# STM32.net
KiCad netlist of a schematic drawn in Altium Designer
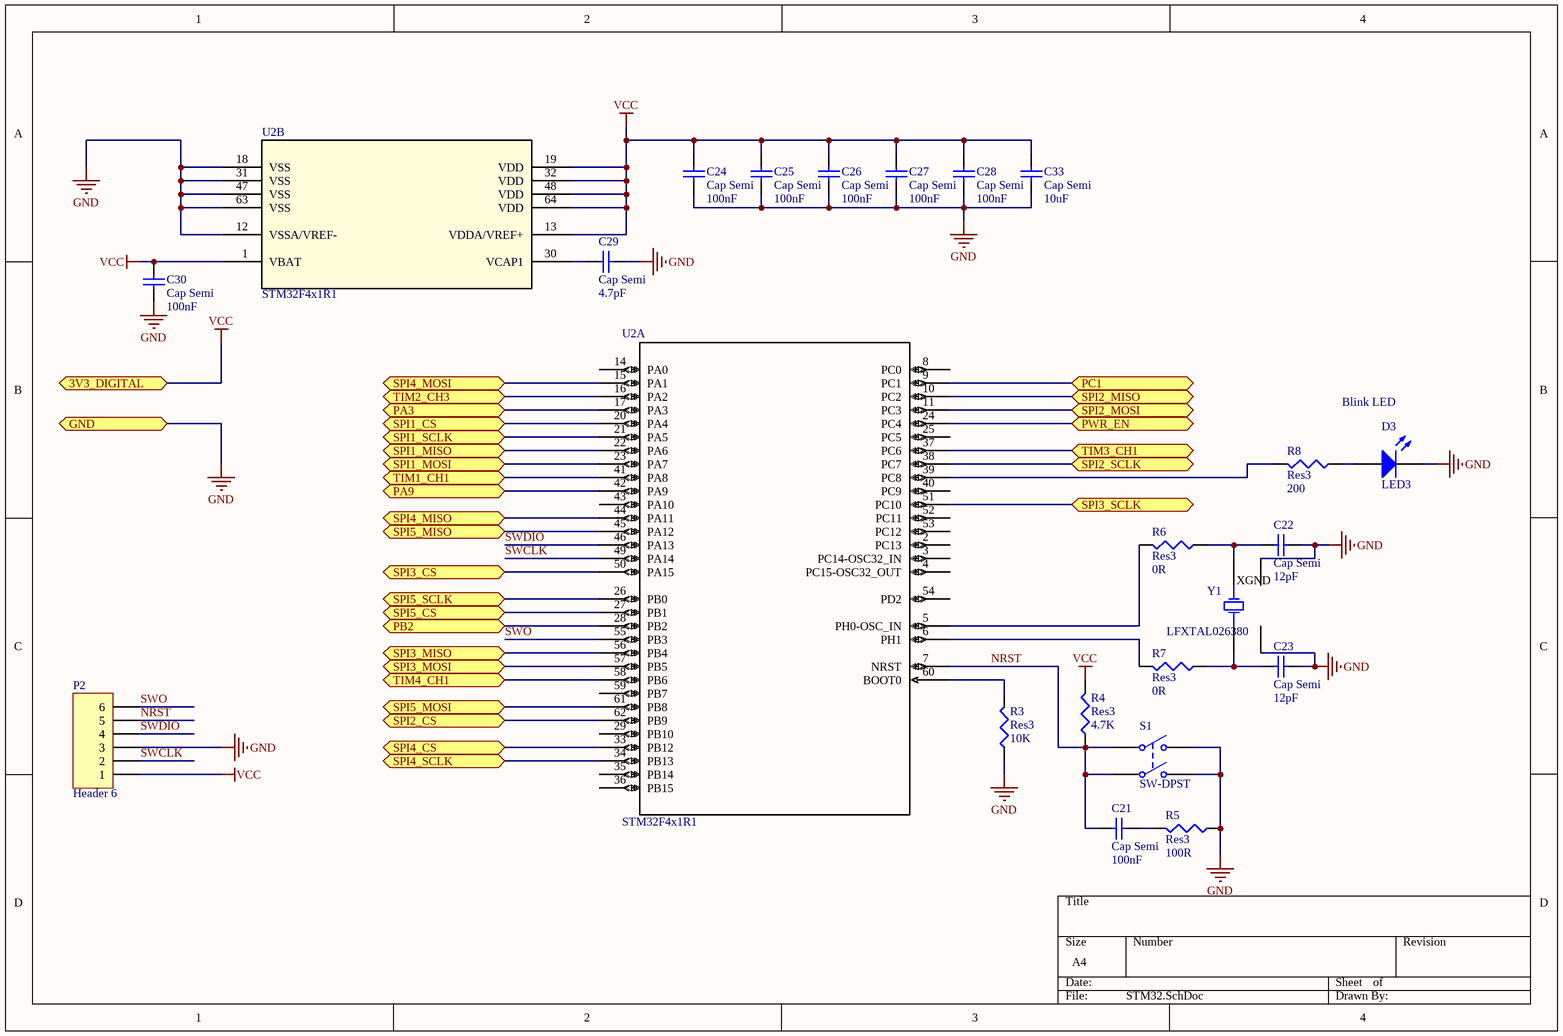
[diagram p0: STM32.SchDoc]

(export (version "E")
  (design (tool "Eeschema 10.0.6"))
  (components
    (comp (ref "C21")
      (value "Cap Semi")
      (footprint "C1206")
      (description "Capacitor (Semiconductor SIM Model)")
      (fields (field (name "ALTIUM_VALUE") "100nF") (field (name "PUBLISHER") "Altium Limited"))
      (libsource (lib "Miscellaneous Devices") (part "Cap Semi"))
    )
    (comp (ref "C22")
      (value "Cap Semi")
      (footprint "C1206")
      (description "Capacitor (Semiconductor SIM Model)")
      (fields (field (name "ALTIUM_VALUE") "12pF") (field (name "PUBLISHER") "Altium Limited"))
      (libsource (lib "Miscellaneous Devices") (part "Cap Semi"))
    )
    (comp (ref "C23")
      (value "Cap Semi")
      (footprint "C1206")
      (description "Capacitor (Semiconductor SIM Model)")
      (fields (field (name "ALTIUM_VALUE") "12pF") (field (name "PUBLISHER") "Altium Limited"))
      (libsource (lib "Miscellaneous Devices") (part "Cap Semi"))
    )
    (comp (ref "C24")
      (value "Cap Semi")
      (footprint "C1206")
      (description "Capacitor (Semiconductor SIM Model)")
      (fields (field (name "ALTIUM_VALUE") "100nF") (field (name "PUBLISHER") "Altium Limited"))
      (libsource (lib "Miscellaneous Devices") (part "Cap Semi"))
    )
    (comp (ref "C25")
      (value "Cap Semi")
      (footprint "C1206")
      (description "Capacitor (Semiconductor SIM Model)")
      (fields (field (name "ALTIUM_VALUE") "100nF") (field (name "PUBLISHER") "Altium Limited"))
      (libsource (lib "Miscellaneous Devices") (part "Cap Semi"))
    )
    (comp (ref "C26")
      (value "Cap Semi")
      (footprint "C1206")
      (description "Capacitor (Semiconductor SIM Model)")
      (fields (field (name "ALTIUM_VALUE") "100nF") (field (name "PUBLISHER") "Altium Limited"))
      (libsource (lib "Miscellaneous Devices") (part "Cap Semi"))
    )
    (comp (ref "C27")
      (value "Cap Semi")
      (footprint "C1206")
      (description "Capacitor (Semiconductor SIM Model)")
      (fields (field (name "ALTIUM_VALUE") "100nF") (field (name "PUBLISHER") "Altium Limited"))
      (libsource (lib "Miscellaneous Devices") (part "Cap Semi"))
    )
    (comp (ref "C28")
      (value "Cap Semi")
      (footprint "C1206")
      (description "Capacitor (Semiconductor SIM Model)")
      (fields (field (name "ALTIUM_VALUE") "100nF") (field (name "PUBLISHER") "Altium Limited"))
      (libsource (lib "Miscellaneous Devices") (part "Cap Semi"))
    )
    (comp (ref "C29")
      (value "Cap Semi")
      (footprint "C1206")
      (description "Capacitor (Semiconductor SIM Model)")
      (fields (field (name "ALTIUM_VALUE") "4.7pF") (field (name "PUBLISHER") "Altium Limited"))
      (libsource (lib "Miscellaneous Devices") (part "Cap Semi"))
    )
    (comp (ref "C30")
      (value "Cap Semi")
      (footprint "C1206")
      (description "Capacitor (Semiconductor SIM Model)")
      (fields (field (name "ALTIUM_VALUE") "100nF") (field (name "PUBLISHER") "Altium Limited"))
      (libsource (lib "Miscellaneous Devices") (part "Cap Semi"))
    )
    (comp (ref "C33")
      (value "Cap Semi")
      (footprint "C1210")
      (description "Capacitor (Semiconductor SIM Model)")
      (fields (field (name "ALTIUM_VALUE") "10uF") (field (name "PUBLISHER") "Altium Limited"))
      (libsource (lib "Miscellaneous Devices") (part "Cap Semi"))
    )
    (comp (ref "D3")
      (value "LED3")
      (footprint "3.5X2.8X1.9")
      (description "Typical BLUE SiC LED")
      (fields (field (name "PUBLISHER") "Altium Limited"))
      (libsource (lib "Miscellaneous Devices") (part "LED3"))
    )
    (comp (ref "P2")
      (value "Header 6")
      (footprint "HDR1X6")
      (description "Header, 6-Pin")
      (fields (field (name "PUBLISHER") "Altium Limited"))
      (libsource (lib "Miscellaneous Connectors") (part "Header 6"))
    )
    (comp (ref "R3")
      (value "Res3")
      (footprint "J1-0603")
      (description "Resistor")
      (fields (field (name "ALTIUM_VALUE") "10K") (field (name "PUBLISHER") "Altium Limited"))
      (libsource (lib "Miscellaneous Devices") (part "Res3"))
    )
    (comp (ref "R4")
      (value "Res3")
      (footprint "J1-0603")
      (description "Resistor")
      (fields (field (name "ALTIUM_VALUE") "4.7K") (field (name "PUBLISHER") "Altium Limited"))
      (libsource (lib "Miscellaneous Devices") (part "Res3"))
    )
    (comp (ref "R5")
      (value "Res3")
      (footprint "J1-0603")
      (description "Resistor")
      (fields (field (name "ALTIUM_VALUE") "100R") (field (name "PUBLISHER") "Altium Limited"))
      (libsource (lib "Miscellaneous Devices") (part "Res3"))
    )
    (comp (ref "R6")
      (value "Res3")
      (footprint "J1-0603")
      (description "Resistor")
      (fields (field (name "ALTIUM_VALUE") "0R") (field (name "PUBLISHER") "Altium Limited"))
      (libsource (lib "Miscellaneous Devices") (part "Res3"))
    )
    (comp (ref "R7")
      (value "Res3")
      (footprint "J1-0603")
      (description "Resistor")
      (fields (field (name "ALTIUM_VALUE") "0R") (field (name "PUBLISHER") "Altium Limited"))
      (libsource (lib "Miscellaneous Devices") (part "Res3"))
    )
    (comp (ref "R8")
      (value "Res3")
      (footprint "J1-0603")
      (description "Resistor")
      (fields (field (name "ALTIUM_VALUE") "200") (field (name "PUBLISHER") "Altium Limited"))
      (libsource (lib "Miscellaneous Devices") (part "Res3"))
    )
    (comp (ref "S1")
      (value "SW-DPST")
      (footprint "RPi_sensor_expansion_board:TACT_SWITCH")
      (description "Double-Pole, Single-Throw Switch")
      (fields (field (name "PUBLISHER") "Altium Limited"))
      (libsource (lib "RPi_sensor_expansion_board_library") (part "SW-DPST"))
    )
    (comp (ref "U2")
      (value "STM32F4x1R1")
      (footprint "LQFP64-10x10mm")
      (description "Imported")
      (fields
        (field (name "MANUFACTURER_PART_NUMBER") "stm32f4x1r1")
        (field (name "COPYRIGHT") "Copyright (C) 2016 Accelerated Designs. All rights reserved")
      )
      (libsource (lib "RPi_sensor_expansion_board_library") (part "STM32F4x1R1"))
    )
    (comp (ref "Y1")
      (value "LFXTAL026380")
      (footprint "12SMX-B")
      (libsource (lib "RPi_sensor_expansion_board_library") (part "LFXTAL026380"))
    )
  )
  (nets
    (net (code "1") (name "/NRST") (class "Default")
      (node (ref "C21") (pin "2") (pinfunction "2_2") (pintype "passive"))
      (node (ref "P2") (pin "5") (pinfunction "5_5") (pintype "passive"))
      (node (ref "R4") (pin "1") (pinfunction "1_1") (pintype "passive"))
      (node (ref "S1") (pin "1") (pinfunction "COMMON1_1") (pintype "passive"))
      (node (ref "S1") (pin "3") (pinfunction "COMMON2_3") (pintype "passive"))
      (node (ref "U2") (pin "7") (pinfunction "NRST_7") (pintype "bidirectional"))
    )
    (net (code "2") (name "/PA3") (class "Default")
      (node (ref "U2") (pin "17") (pinfunction "PA3_17") (pintype "bidirectional"))
    )
    (net (code "3") (name "/PA9") (class "Default")
      (node (ref "U2") (pin "42") (pinfunction "PA9_42") (pintype "bidirectional"))
    )
    (net (code "4") (name "/PB2") (class "Default")
      (node (ref "U2") (pin "28") (pinfunction "PB2_28") (pintype "bidirectional"))
    )
    (net (code "5") (name "/PC1") (class "Default")
      (node (ref "U2") (pin "9") (pinfunction "PC1_9") (pintype "bidirectional"))
    )
    (net (code "6") (name "/PWR_EN") (class "Default")
      (node (ref "U2") (pin "24") (pinfunction "PC4_24") (pintype "bidirectional"))
    )
    (net (code "7") (name "/SPI1_CS") (class "Default")
      (node (ref "U2") (pin "20") (pinfunction "PA4_20") (pintype "bidirectional"))
    )
    (net (code "8") (name "/SPI1_MISO") (class "Default")
      (node (ref "U2") (pin "22") (pinfunction "PA6_22") (pintype "bidirectional"))
    )
    (net (code "9") (name "/SPI1_MOSI") (class "Default")
      (node (ref "U2") (pin "23") (pinfunction "PA7_23") (pintype "bidirectional"))
    )
    (net (code "10") (name "/SPI1_SCLK") (class "Default")
      (node (ref "U2") (pin "21") (pinfunction "PA5_21") (pintype "bidirectional"))
    )
    (net (code "11") (name "/SPI2_CS") (class "Default")
      (node (ref "U2") (pin "62") (pinfunction "PB9_62") (pintype "bidirectional"))
    )
    (net (code "12") (name "/SPI2_MISO") (class "Default")
      (node (ref "U2") (pin "10") (pinfunction "PC2_10") (pintype "bidirectional"))
    )
    (net (code "13") (name "/SPI2_MOSI") (class "Default")
      (node (ref "U2") (pin "11") (pinfunction "PC3_11") (pintype "bidirectional"))
    )
    (net (code "14") (name "/SPI2_SCLK") (class "Default")
      (node (ref "U2") (pin "38") (pinfunction "PC7_38") (pintype "bidirectional"))
    )
    (net (code "15") (name "/SPI3_CS") (class "Default")
      (node (ref "U2") (pin "50") (pinfunction "PA15_50") (pintype "bidirectional"))
    )
    (net (code "16") (name "/SPI3_MISO") (class "Default")
      (node (ref "U2") (pin "56") (pinfunction "PB4_56") (pintype "bidirectional"))
    )
    (net (code "17") (name "/SPI3_MOSI") (class "Default")
      (node (ref "U2") (pin "57") (pinfunction "PB5_57") (pintype "bidirectional"))
    )
    (net (code "18") (name "/SPI3_SCLK") (class "Default")
      (node (ref "U2") (pin "51") (pinfunction "PC10_51") (pintype "bidirectional"))
    )
    (net (code "19") (name "/SPI4_CS") (class "Default")
      (node (ref "U2") (pin "33") (pinfunction "PB12_33") (pintype "bidirectional"))
    )
    (net (code "20") (name "/SPI4_MISO") (class "Default")
      (node (ref "U2") (pin "44") (pinfunction "PA11_44") (pintype "bidirectional"))
    )
    (net (code "21") (name "/SPI4_MOSI") (class "Default")
      (node (ref "U2") (pin "15") (pinfunction "PA1_15") (pintype "bidirectional"))
    )
    (net (code "22") (name "/SPI4_SCLK") (class "Default")
      (node (ref "U2") (pin "34") (pinfunction "PB13_34") (pintype "bidirectional"))
    )
    (net (code "23") (name "/SPI5_CS") (class "Default")
      (node (ref "U2") (pin "27") (pinfunction "PB1_27") (pintype "bidirectional"))
    )
    (net (code "24") (name "/SPI5_MISO") (class "Default")
      (node (ref "U2") (pin "45") (pinfunction "PA12_45") (pintype "bidirectional"))
    )
    (net (code "25") (name "/SPI5_MOSI") (class "Default")
      (node (ref "U2") (pin "61") (pinfunction "PB8_61") (pintype "bidirectional"))
    )
    (net (code "26") (name "/SPI5_SCLK") (class "Default")
      (node (ref "U2") (pin "26") (pinfunction "PB0_26") (pintype "bidirectional"))
    )
    (net (code "27") (name "/SWCLK") (class "Default")
      (node (ref "P2") (pin "2") (pinfunction "2_2") (pintype "passive"))
      (node (ref "U2") (pin "49") (pinfunction "PA14_49") (pintype "bidirectional"))
    )
    (net (code "28") (name "/SWDIO") (class "Default")
      (node (ref "P2") (pin "4") (pinfunction "4_4") (pintype "passive"))
      (node (ref "U2") (pin "46") (pinfunction "PA13_46") (pintype "bidirectional"))
    )
    (net (code "29") (name "/SWO") (class "Default")
      (node (ref "P2") (pin "6") (pinfunction "6_6") (pintype "passive"))
      (node (ref "U2") (pin "55") (pinfunction "PB3_55") (pintype "bidirectional"))
    )
    (net (code "30") (name "/TIM1_CH1") (class "Default")
      (node (ref "U2") (pin "41") (pinfunction "PA8_41") (pintype "bidirectional"))
    )
    (net (code "31") (name "/TIM2_CH3") (class "Default")
      (node (ref "U2") (pin "16") (pinfunction "PA2_16") (pintype "bidirectional"))
    )
    (net (code "32") (name "/TIM3_CH1") (class "Default")
      (node (ref "U2") (pin "37") (pinfunction "PC6_37") (pintype "bidirectional"))
    )
    (net (code "33") (name "/TIM4_CH1") (class "Default")
      (node (ref "U2") (pin "58") (pinfunction "PB6_58") (pintype "bidirectional"))
    )
    (net (code "34") (name "GND") (class "Default")
      (node (ref "C22") (pin "1") (pinfunction "1_1") (pintype "passive"))
      (node (ref "C23") (pin "1") (pinfunction "1_1") (pintype "passive"))
      (node (ref "C24") (pin "2") (pinfunction "2_2") (pintype "passive"))
      (node (ref "C25") (pin "2") (pinfunction "2_2") (pintype "passive"))
      (node (ref "C26") (pin "2") (pinfunction "2_2") (pintype "passive"))
      (node (ref "C27") (pin "2") (pinfunction "2_2") (pintype "passive"))
      (node (ref "C28") (pin "2") (pinfunction "2_2") (pintype "passive"))
      (node (ref "C29") (pin "1") (pinfunction "1_1") (pintype "passive"))
      (node (ref "C30") (pin "1") (pinfunction "1_1") (pintype "passive"))
      (node (ref "C33") (pin "2") (pinfunction "2_2") (pintype "passive"))
      (node (ref "D3") (pin "2") (pinfunction "K_2") (pintype "passive"))
      (node (ref "P2") (pin "3") (pinfunction "3_3") (pintype "passive"))
      (node (ref "R3") (pin "1") (pinfunction "1_1") (pintype "passive"))
      (node (ref "R5") (pin "1") (pinfunction "1_1") (pintype "passive"))
      (node (ref "S1") (pin "2") (pinfunction "NO1_2") (pintype "passive"))
      (node (ref "S1") (pin "4") (pinfunction "NO2_4") (pintype "passive"))
      (node (ref "U2") (pin "12") (pinfunction "VSSA/VREF-_12") (pintype "power_in"))
      (node (ref "U2") (pin "18") (pinfunction "VSS_18") (pintype "power_in"))
      (node (ref "U2") (pin "31") (pinfunction "VSS_31") (pintype "power_in"))
      (node (ref "U2") (pin "47") (pinfunction "VSS_47") (pintype "power_in"))
      (node (ref "U2") (pin "63") (pinfunction "VSS_63") (pintype "power_in"))
      (node (ref "Y1") (pin "2") (pinfunction "OSC2_2") (pintype "passive"))
      (node (ref "Y1") (pin "4") (pinfunction "OSC1_4") (pintype "passive"))
    )
    (net (code "35") (name "Net-(C21-Pad1)") (class "Default")
      (node (ref "C21") (pin "1") (pinfunction "1_1") (pintype "passive"))
      (node (ref "R5") (pin "2") (pinfunction "2_2") (pintype "passive"))
    )
    (net (code "36") (name "Net-(C22-Pad2)") (class "Default")
      (node (ref "C22") (pin "2") (pinfunction "2_2") (pintype "passive"))
      (node (ref "R6") (pin "1") (pinfunction "1_1") (pintype "passive"))
      (node (ref "Y1") (pin "3") (pinfunction "OSC2_3") (pintype "passive"))
    )
    (net (code "37") (name "Net-(C23-Pad2)") (class "Default")
      (node (ref "C23") (pin "2") (pinfunction "2_2") (pintype "passive"))
      (node (ref "R7") (pin "1") (pinfunction "1_1") (pintype "passive"))
      (node (ref "Y1") (pin "1") (pinfunction "OSC1_1") (pintype "passive"))
    )
    (net (code "38") (name "Net-(D3-A)") (class "Default")
      (node (ref "D3") (pin "1") (pinfunction "A_1") (pintype "passive"))
      (node (ref "R8") (pin "1") (pinfunction "1_1") (pintype "passive"))
    )
    (net (code "39") (name "Net-(U2A-BOOT0)") (class "Default")
      (node (ref "R3") (pin "2") (pinfunction "2_2") (pintype "passive"))
      (node (ref "U2") (pin "60") (pinfunction "BOOT0_60") (pintype "input"))
    )
    (net (code "40") (name "Net-(U2A-PC8)") (class "Default")
      (node (ref "R8") (pin "2") (pinfunction "2_2") (pintype "passive"))
      (node (ref "U2") (pin "39") (pinfunction "PC8_39") (pintype "bidirectional"))
    )
    (net (code "41") (name "Net-(U2A-PH0-OSC_IN)") (class "Default")
      (node (ref "R6") (pin "2") (pinfunction "2_2") (pintype "passive"))
      (node (ref "U2") (pin "5") (pinfunction "PH0-OSC_IN_5") (pintype "bidirectional"))
    )
    (net (code "42") (name "Net-(U2A-PH1)") (class "Default")
      (node (ref "R7") (pin "2") (pinfunction "2_2") (pintype "passive"))
      (node (ref "U2") (pin "6") (pinfunction "PH1_6") (pintype "bidirectional"))
    )
    (net (code "43") (name "Net-(U2B-VCAP1)") (class "Default")
      (node (ref "C29") (pin "2") (pinfunction "2_2") (pintype "passive"))
      (node (ref "U2") (pin "30") (pinfunction "VCAP1_30") (pintype "power_in"))
    )
    (net (code "44") (name "VCC") (class "Default")
      (node (ref "C24") (pin "1") (pinfunction "1_1") (pintype "passive"))
      (node (ref "C25") (pin "1") (pinfunction "1_1") (pintype "passive"))
      (node (ref "C26") (pin "1") (pinfunction "1_1") (pintype "passive"))
      (node (ref "C27") (pin "1") (pinfunction "1_1") (pintype "passive"))
      (node (ref "C28") (pin "1") (pinfunction "1_1") (pintype "passive"))
      (node (ref "C30") (pin "2") (pinfunction "2_2") (pintype "passive"))
      (node (ref "C33") (pin "1") (pinfunction "1_1") (pintype "passive"))
      (node (ref "P2") (pin "1") (pinfunction "1_1") (pintype "passive"))
      (node (ref "R4") (pin "2") (pinfunction "2_2") (pintype "passive"))
      (node (ref "U2") (pin "1") (pinfunction "VBAT_1") (pintype "power_in"))
      (node (ref "U2") (pin "13") (pinfunction "VDDA/VREF+_13") (pintype "power_in"))
      (node (ref "U2") (pin "19") (pinfunction "VDD_19") (pintype "power_in"))
      (node (ref "U2") (pin "32") (pinfunction "VDD_32") (pintype "power_in"))
      (node (ref "U2") (pin "48") (pinfunction "VDD_48") (pintype "power_in"))
      (node (ref "U2") (pin "64") (pinfunction "VDD_64") (pintype "power_in"))
    )
    (net (code "45") (name "unconnected-(U2A-PA0-Pad14)") (class "Default")
      (node (ref "U2") (pin "14") (pinfunction "PA0_14") (pintype "bidirectional"))
    )
    (net (code "46") (name "unconnected-(U2A-PA10-Pad43)") (class "Default")
      (node (ref "U2") (pin "43") (pinfunction "PA10_43") (pintype "bidirectional"))
    )
    (net (code "47") (name "unconnected-(U2A-PB7-Pad59)") (class "Default")
      (node (ref "U2") (pin "59") (pinfunction "PB7_59") (pintype "bidirectional"))
    )
    (net (code "48") (name "unconnected-(U2A-PB10-Pad29)") (class "Default")
      (node (ref "U2") (pin "29") (pinfunction "PB10_29") (pintype "bidirectional"))
    )
    (net (code "49") (name "unconnected-(U2A-PB14-Pad35)") (class "Default")
      (node (ref "U2") (pin "35") (pinfunction "PB14_35") (pintype "bidirectional"))
    )
    (net (code "50") (name "unconnected-(U2A-PB15-Pad36)") (class "Default")
      (node (ref "U2") (pin "36") (pinfunction "PB15_36") (pintype "bidirectional"))
    )
    (net (code "51") (name "unconnected-(U2A-PC0-Pad8)") (class "Default")
      (node (ref "U2") (pin "8") (pinfunction "PC0_8") (pintype "bidirectional"))
    )
    (net (code "52") (name "unconnected-(U2A-PC5-Pad25)") (class "Default")
      (node (ref "U2") (pin "25") (pinfunction "PC5_25") (pintype "bidirectional"))
    )
    (net (code "53") (name "unconnected-(U2A-PC9-Pad40)") (class "Default")
      (node (ref "U2") (pin "40") (pinfunction "PC9_40") (pintype "bidirectional"))
    )
    (net (code "54") (name "unconnected-(U2A-PC11-Pad52)") (class "Default")
      (node (ref "U2") (pin "52") (pinfunction "PC11_52") (pintype "bidirectional"))
    )
    (net (code "55") (name "unconnected-(U2A-PC12-Pad53)") (class "Default")
      (node (ref "U2") (pin "53") (pinfunction "PC12_53") (pintype "bidirectional"))
    )
    (net (code "56") (name "unconnected-(U2A-PC13-Pad2)") (class "Default")
      (node (ref "U2") (pin "2") (pinfunction "PC13_2") (pintype "bidirectional"))
    )
    (net (code "57") (name "unconnected-(U2A-PC14-OSC32_IN-Pad3)") (class "Default")
      (node (ref "U2") (pin "3") (pinfunction "PC14-OSC32_IN_3") (pintype "bidirectional"))
    )
    (net (code "58") (name "unconnected-(U2A-PC15-OSC32_OUT-Pad4)") (class "Default")
      (node (ref "U2") (pin "4") (pinfunction "PC15-OSC32_OUT_4") (pintype "bidirectional"))
    )
    (net (code "59") (name "unconnected-(U2A-PD2-Pad54)") (class "Default")
      (node (ref "U2") (pin "54") (pinfunction "PD2_54") (pintype "bidirectional"))
    )
  )
)
